# Voeding_Soldeerbout.net
KiCad netlist of a schematic drawn in Altium Designer
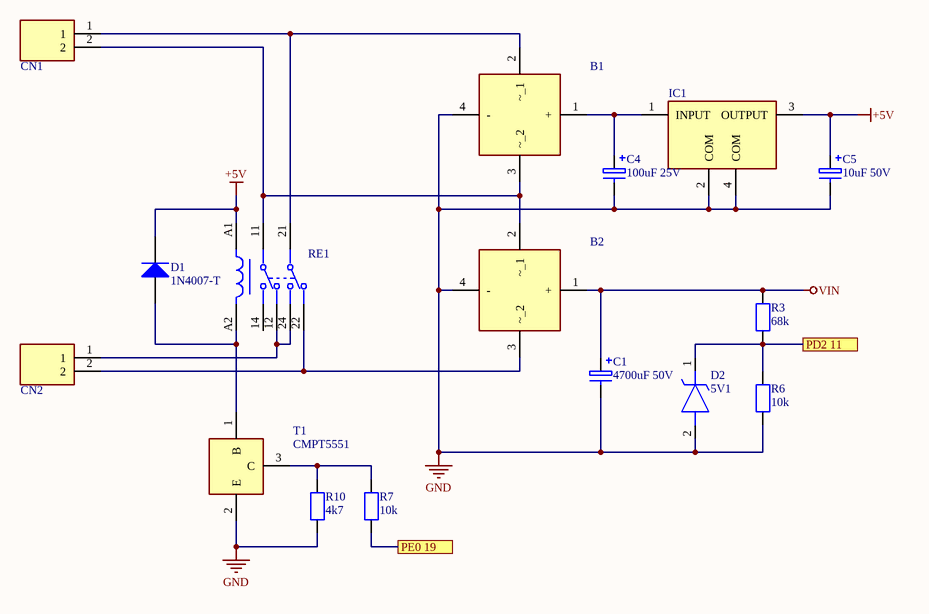
[diagram p0: Voeding_Soldeerbout.SchDoc]

(export (version "E")
  (design (tool "Eeschema 10.0.6"))
  (components
    (comp (ref "B1")
      (value "GBU6J")
      (footprint "PcbLib1:Bridge Rectifier")
      (description "Bridge Rectifier")
      (libsource (lib "Schlib1") (part "GBU6J"))
    )
    (comp (ref "B2")
      (value "GBU6J")
      (footprint "PcbLib1:Bridge Rectifier")
      (description "Bridge Rectifier")
      (libsource (lib "Schlib1") (part "GBU6J"))
    )
    (comp (ref "C1")
      (value "4700uF 50V")
      (footprint "Elco 4700uF 50V")
      (fields
        (field (name "PART NUMBER") "02015A270JAT2A")
        (field (name "MANUFACTURER") "AVX Interconnect / Elco")
      )
      (libsource (lib "Schlib1") (part "Condensator Elco"))
    )
    (comp (ref "C4")
      (value "100uF 25V")
      (footprint "Elco 100uF 25V")
      (fields
        (field (name "PART NUMBER") "02015A270JAT2A")
        (field (name "MANUFACTURER") "AVX Interconnect / Elco")
      )
      (libsource (lib "Schlib1") (part "Condensator Elco"))
    )
    (comp (ref "C5")
      (value "10uF 50V")
      (footprint "Elco 100uF 25V")
      (fields
        (field (name "PART NUMBER") "02015A270JAT2A")
        (field (name "MANUFACTURER") "AVX Interconnect / Elco")
      )
      (libsource (lib "Schlib1") (part "Condensator Elco"))
    )
    (comp (ref "CN1")
      (value "282836-2")
      (footprint "SamacSys:2828362")
      (description "Connector")
      (libsource (lib "Schlib1") (part "Schroefconnector 2 Pin"))
    )
    (comp (ref "CN2")
      (value "282836-2")
      (footprint "SamacSys:2828362")
      (description "Connector")
      (libsource (lib "Schlib1") (part "Schroefconnector 2 Pin"))
    )
    (comp (ref "D1")
      (value "1N4007-T")
      (footprint "DIOD-DO-41-P-2_V")
      (description "1.0 A Rectifier, 8 pF, 1000 V, -65 to 150 degC, 2-Pin DO-41 Plastic, RoHS, Tape and Reel")
      (fields (field (name "MANUFACTURER") "Diodes Inc"))
      (libsource (lib "Altium Content Vault") (part "DIOD-D-A1K2-2"))
    )
    (comp (ref "D2")
      (value "5V1")
      (footprint "SamacSys:DIOAD1068W53L380D172")
      (description "Zener Diode")
      (fields
        (field (name "MOUSER2 PART NUMBER") "512-1N5231CTR")
        (field (name "MANUFACTURER_PART_NUMBER") "1N5231CTR")
      )
      (libsource (lib "*") (part "1N5231CTR"))
    )
    (comp (ref "IC1")
      (value "TL780-05CKTTR")
      (footprint "DC-DC Convertor")
      (description "IC REG LIN 5V 1.5A DDPAK/TO263-3")
      (libsource (lib "Schlib1") (part "DC/DC Convertor"))
    )
    (comp (ref "R3")
      (value "68k")
      (footprint "0805")
      (fields (field (name "MANUFACTURER") "Vishay Dale") (field (name "PART NUMBER") "CRCW08050000Z0EA"))
      (libsource (lib "Schlib1") (part "Resistor 0805"))
    )
    (comp (ref "R6")
      (value "10k")
      (footprint "0805")
      (fields (field (name "MANUFACTURER") "Vishay Dale") (field (name "PART NUMBER") "CRCW08050000Z0EA"))
      (libsource (lib "Schlib1") (part "Resistor 0805"))
    )
    (comp (ref "R7")
      (value "10k")
      (footprint "0805")
      (fields (field (name "MANUFACTURER") "Vishay Dale") (field (name "PART NUMBER") "CRCW08050000Z0EA"))
      (libsource (lib "Schlib1") (part "Resistor 0805"))
    )
    (comp (ref "R10")
      (value "4k7")
      (footprint "0805")
      (fields (field (name "MANUFACTURER") "Vishay Dale") (field (name "PART NUMBER") "CRCW08050000Z0EA"))
      (libsource (lib "Schlib1") (part "Resistor 0805"))
    )
    (comp (ref "RE1")
      (value "RT424005")
      (footprint "FP-RT424005-MFG")
      (description "RELAY GENERAL PURPOSE DPDT 8A 5V")
      (fields
        (field (name "OCTOPART") "https://octopart.com/5-1393243-9-te+connectivity-41835766")
        (field (name "MANUFACTURER") "TE Connectivity")
      )
      (libsource (lib "Altium Content Vault") (part "41b11f646d56a8146f21bf1e8c88c79"))
    )
    (comp (ref "T1")
      (value "CMPT5551")
      (footprint "SamacSys:SOT95P230X109-3N")
      (description "Transistor")
      (fields (field (name "MANUFACTURER_PART_NUMBER") "CMPT5551 TR PBFREE"))
      (libsource (lib "Schlib1") (part "CMPT5551"))
    )
  )
  (nets
    (net (code "1") (name "+5V") (class "Default")
      (node (ref "C5") (pin "1") (pinfunction "1_1") (pintype "passive"))
      (node (ref "D1") (pin "2") (pinfunction "K_2") (pintype "passive"))
      (node (ref "IC1") (pin "3") (pinfunction "OUTPUT_3") (pintype "power_in"))
      (node (ref "RE1") (pin "A1") (pinfunction "A1_A1") (pintype "passive"))
    )
    (net (code "2") (name "/PD2 11") (class "Default")
      (node (ref "D2") (pin "1") (pinfunction "K_1") (pintype "passive"))
      (node (ref "R3") (pin "1") (pinfunction "1_1") (pintype "passive"))
      (node (ref "R6") (pin "2") (pinfunction "2_2") (pintype "passive"))
    )
    (net (code "3") (name "/PE0 19") (class "Default")
      (node (ref "R7") (pin "1") (pinfunction "1_1") (pintype "passive"))
    )
    (net (code "4") (name "GND") (class "Default")
      (node (ref "B1") (pin "4") (pinfunction "-_4") (pintype "passive"))
      (node (ref "B2") (pin "4") (pinfunction "-_4") (pintype "passive"))
      (node (ref "C1") (pin "2") (pinfunction "2_2") (pintype "passive"))
      (node (ref "C4") (pin "2") (pinfunction "2_2") (pintype "passive"))
      (node (ref "C5") (pin "2") (pinfunction "2_2") (pintype "passive"))
      (node (ref "D2") (pin "2") (pinfunction "A_2") (pintype "passive"))
      (node (ref "IC1") (pin "2") (pinfunction "COM_2") (pintype "passive"))
      (node (ref "IC1") (pin "4") (pinfunction "COM_4") (pintype "passive"))
      (node (ref "R10") (pin "1") (pinfunction "1_1") (pintype "passive"))
      (node (ref "R6") (pin "1") (pinfunction "1_1") (pintype "passive"))
      (node (ref "T1") (pin "2") (pinfunction "E_2") (pintype "passive"))
    )
    (net (code "5") (name "Net-(B1-+)") (class "Default")
      (node (ref "B1") (pin "1") (pinfunction "+_1") (pintype "passive"))
      (node (ref "C4") (pin "1") (pinfunction "1_1") (pintype "passive"))
      (node (ref "IC1") (pin "1") (pinfunction "INPUT_1") (pintype "power_in"))
    )
    (net (code "6") (name "Net-(B1-~_1)") (class "Default")
      (node (ref "B1") (pin "2") (pinfunction "~_1_2") (pintype "passive"))
      (node (ref "CN1") (pin "1") (pinfunction "1_1") (pintype "passive"))
      (node (ref "RE1") (pin "21") (pinfunction "21_21") (pintype "passive"))
    )
    (net (code "7") (name "Net-(B1-~_2)") (class "Default")
      (node (ref "B1") (pin "3") (pinfunction "~_2_3") (pintype "passive"))
      (node (ref "B2") (pin "2") (pinfunction "~_1_2") (pintype "passive"))
      (node (ref "CN1") (pin "2") (pinfunction "2_2") (pintype "passive"))
      (node (ref "RE1") (pin "11") (pinfunction "11_11") (pintype "passive"))
    )
    (net (code "8") (name "Net-(B2-~_2)") (class "Default")
      (node (ref "B2") (pin "3") (pinfunction "~_2_3") (pintype "passive"))
      (node (ref "CN2") (pin "2") (pinfunction "2_2") (pintype "passive"))
      (node (ref "RE1") (pin "22") (pinfunction "22_22") (pintype "passive"))
    )
    (net (code "9") (name "Net-(CN2-Pad1)") (class "Default")
      (node (ref "CN2") (pin "1") (pinfunction "1_1") (pintype "passive"))
      (node (ref "RE1") (pin "12") (pinfunction "12_12") (pintype "passive"))
      (node (ref "RE1") (pin "24") (pinfunction "24_24") (pintype "passive"))
    )
    (net (code "10") (name "Net-(D1-A)") (class "Default")
      (node (ref "D1") (pin "1") (pinfunction "A_1") (pintype "passive"))
      (node (ref "RE1") (pin "A2") (pinfunction "A2_A2") (pintype "passive"))
      (node (ref "T1") (pin "1") (pinfunction "B_1") (pintype "passive"))
    )
    (net (code "11") (name "Net-(T1-C)") (class "Default")
      (node (ref "R10") (pin "2") (pinfunction "2_2") (pintype "passive"))
      (node (ref "R7") (pin "2") (pinfunction "2_2") (pintype "passive"))
      (node (ref "T1") (pin "3") (pinfunction "C_3") (pintype "passive"))
    )
    (net (code "12") (name "VIN") (class "Default")
      (node (ref "B2") (pin "1") (pinfunction "+_1") (pintype "passive"))
      (node (ref "C1") (pin "1") (pinfunction "1_1") (pintype "passive"))
      (node (ref "R3") (pin "2") (pinfunction "2_2") (pintype "passive"))
    )
    (net (code "13") (name "unconnected-(RE1-Pad14)") (class "Default")
      (node (ref "RE1") (pin "14") (pinfunction "14_14") (pintype "passive"))
    )
  )
)
